# esp32_db_v0.net
KiCad netlist of a schematic drawn in EAGLE
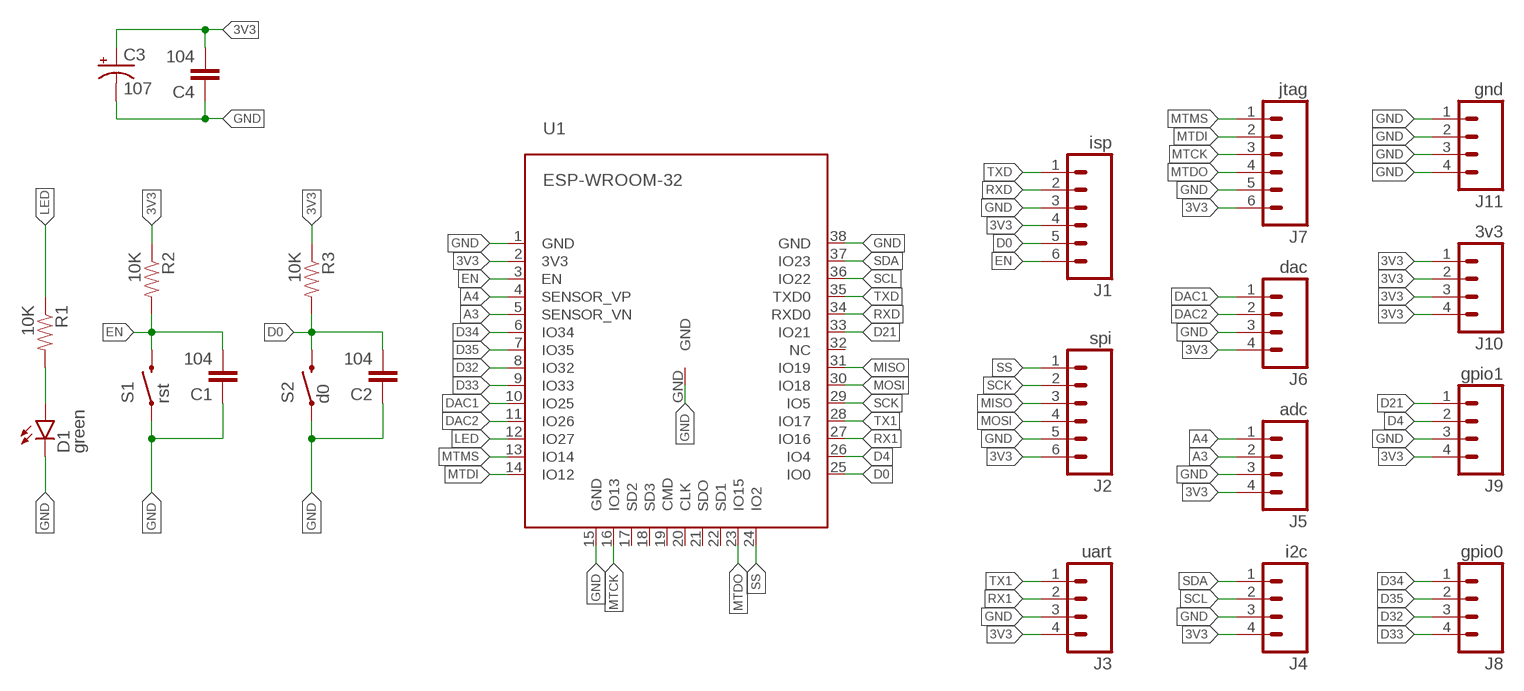
[diagram p0: schematic, sheet 1]

(export (version "E")
  (design (tool "Eeschema 10.0.6"))
  (components
    (comp (ref "C1")
      (value "104")
      (footprint "eagle-import:0603-CAP")
      (libsource (lib "eagle-import") (part "CAP0603-CAP"))
    )
    (comp (ref "C2")
      (value "104")
      (footprint "eagle-import:0603-CAP")
      (libsource (lib "eagle-import") (part "CAP0603-CAP"))
    )
    (comp (ref "C3")
      (value "107")
      (footprint "eagle-import:EIA3528-KIT")
      (libsource (lib "eagle-import") (part "CAP_POL3528-KIT"))
    )
    (comp (ref "C4")
      (value "104")
      (footprint "eagle-import:0603-CAP")
      (libsource (lib "eagle-import") (part "CAP0603-CAP"))
    )
    (comp (ref "D1")
      (value "green")
      (footprint "eagle-import:LED-0603-EASY")
      (libsource (lib "eagle-import") (part "LED-EASY"))
    )
    (comp (ref "J1")
      (value "isp")
      (footprint "eagle-import:1X06_NO_SILK")
      (libsource (lib "eagle-import") (part "M06NO_SILK_FEMALE_PTH"))
    )
    (comp (ref "J2")
      (value "spi")
      (footprint "eagle-import:1X06_NO_SILK")
      (libsource (lib "eagle-import") (part "M06NO_SILK_FEMALE_PTH"))
    )
    (comp (ref "J3")
      (value "uart")
      (footprint "eagle-import:1X04_NO_SILK_ALL_ROUND")
      (libsource (lib "eagle-import") (part "M04NO_SILK_ALL_ROUND"))
    )
    (comp (ref "J4")
      (value "i2c")
      (footprint "eagle-import:1X04_NO_SILK_ALL_ROUND")
      (libsource (lib "eagle-import") (part "M04NO_SILK_ALL_ROUND"))
    )
    (comp (ref "J5")
      (value "adc")
      (footprint "eagle-import:1X04_NO_SILK_ALL_ROUND")
      (libsource (lib "eagle-import") (part "M04NO_SILK_ALL_ROUND"))
    )
    (comp (ref "J6")
      (value "dac")
      (footprint "eagle-import:1X04_NO_SILK_ALL_ROUND")
      (libsource (lib "eagle-import") (part "M04NO_SILK_ALL_ROUND"))
    )
    (comp (ref "J7")
      (value "jtag")
      (footprint "eagle-import:1X06_NO_SILK")
      (libsource (lib "eagle-import") (part "M06NO_SILK_FEMALE_PTH"))
    )
    (comp (ref "J8")
      (value "gpio0")
      (footprint "eagle-import:1X04_NO_SILK_ALL_ROUND")
      (libsource (lib "eagle-import") (part "M04NO_SILK_ALL_ROUND"))
    )
    (comp (ref "J9")
      (value "gpio1")
      (footprint "eagle-import:1X04_NO_SILK_ALL_ROUND")
      (libsource (lib "eagle-import") (part "M04NO_SILK_ALL_ROUND"))
    )
    (comp (ref "J10")
      (value "3v3")
      (footprint "eagle-import:1X04_NO_SILK_ALL_ROUND")
      (libsource (lib "eagle-import") (part "M04NO_SILK_ALL_ROUND"))
    )
    (comp (ref "J11")
      (value "gnd")
      (footprint "eagle-import:1X04_NO_SILK_ALL_ROUND")
      (libsource (lib "eagle-import") (part "M04NO_SILK_ALL_ROUND"))
    )
    (comp (ref "R1")
      (value "10K")
      (footprint "eagle-import:0603-RES")
      (libsource (lib "eagle-import") (part "RESISTOR0603-RES"))
    )
    (comp (ref "R2")
      (value "10K")
      (footprint "eagle-import:0603-RES")
      (libsource (lib "eagle-import") (part "RESISTOR0603-RES"))
    )
    (comp (ref "R3")
      (value "10K")
      (footprint "eagle-import:0603-RES")
      (libsource (lib "eagle-import") (part "RESISTOR0603-RES"))
    )
    (comp (ref "S1")
      (value "rst")
      (footprint "eagle-import:TACTILE-PTH")
      (libsource (lib "eagle-import") (part "SWITCH-MOMENTARY-2PTH"))
    )
    (comp (ref "S2")
      (value "d0")
      (footprint "eagle-import:TACTILE-PTH")
      (libsource (lib "eagle-import") (part "SWITCH-MOMENTARY-2PTH"))
    )
    (comp (ref "U1")
      (value "ESP-WROOM-32")
      (footprint "eagle-import:ESP-WROOM-32")
      (libsource (lib "eagle-import") (part "ESP-WROOM-32"))
    )
  )
  (nets
    (net (code "1") (name "3V3") (class "Default")
      (node (ref "C3") (pin "A") (pinfunction "+_A") (pintype "passive"))
      (node (ref "C4") (pin "2") (pinfunction "2_2") (pintype "passive"))
      (node (ref "J1") (pin "4") (pinfunction "4_4") (pintype "passive"))
      (node (ref "J10") (pin "1") (pinfunction "1_1") (pintype "passive"))
      (node (ref "J10") (pin "2") (pinfunction "2_2") (pintype "passive"))
      (node (ref "J10") (pin "3") (pinfunction "3_3") (pintype "passive"))
      (node (ref "J10") (pin "4") (pinfunction "4_4") (pintype "passive"))
      (node (ref "J2") (pin "6") (pinfunction "6_6") (pintype "passive"))
      (node (ref "J3") (pin "4") (pinfunction "4_4") (pintype "passive"))
      (node (ref "J4") (pin "4") (pinfunction "4_4") (pintype "passive"))
      (node (ref "J5") (pin "4") (pinfunction "4_4") (pintype "passive"))
      (node (ref "J6") (pin "4") (pinfunction "4_4") (pintype "passive"))
      (node (ref "J7") (pin "6") (pinfunction "6_6") (pintype "passive"))
      (node (ref "J9") (pin "4") (pinfunction "4_4") (pintype "passive"))
      (node (ref "R2") (pin "1") (pinfunction "1_1") (pintype "passive"))
      (node (ref "R3") (pin "1") (pinfunction "1_1") (pintype "passive"))
      (node (ref "U1") (pin "2") (pinfunction "3V3_2") (pintype "bidirectional"))
    )
    (net (code "2") (name "A3") (class "Default")
      (node (ref "J5") (pin "2") (pinfunction "2_2") (pintype "passive"))
      (node (ref "U1") (pin "5") (pinfunction "SENSOR_VN_5") (pintype "bidirectional"))
    )
    (net (code "3") (name "A4") (class "Default")
      (node (ref "J5") (pin "1") (pinfunction "1_1") (pintype "passive"))
      (node (ref "U1") (pin "4") (pinfunction "SENSOR_VP_4") (pintype "bidirectional"))
    )
    (net (code "4") (name "D0") (class "Default")
      (node (ref "C2") (pin "2") (pinfunction "2_2") (pintype "passive"))
      (node (ref "J1") (pin "5") (pinfunction "5_5") (pintype "passive"))
      (node (ref "R3") (pin "2") (pinfunction "2_2") (pintype "passive"))
      (node (ref "S2") (pin "3") (pinfunction "2_3") (pintype "passive"))
      (node (ref "U1") (pin "25") (pinfunction "IO0_25") (pintype "bidirectional"))
    )
    (net (code "5") (name "D4") (class "Default")
      (node (ref "J9") (pin "2") (pinfunction "2_2") (pintype "passive"))
      (node (ref "U1") (pin "26") (pinfunction "IO4_26") (pintype "bidirectional"))
    )
    (net (code "6") (name "D21") (class "Default")
      (node (ref "J9") (pin "1") (pinfunction "1_1") (pintype "passive"))
      (node (ref "U1") (pin "33") (pinfunction "IO21_33") (pintype "bidirectional"))
    )
    (net (code "7") (name "D32") (class "Default")
      (node (ref "J8") (pin "3") (pinfunction "3_3") (pintype "passive"))
      (node (ref "U1") (pin "8") (pinfunction "IO32_8") (pintype "bidirectional"))
    )
    (net (code "8") (name "D33") (class "Default")
      (node (ref "J8") (pin "4") (pinfunction "4_4") (pintype "passive"))
      (node (ref "U1") (pin "9") (pinfunction "IO33_9") (pintype "bidirectional"))
    )
    (net (code "9") (name "D34") (class "Default")
      (node (ref "J8") (pin "1") (pinfunction "1_1") (pintype "passive"))
      (node (ref "U1") (pin "6") (pinfunction "IO34_6") (pintype "bidirectional"))
    )
    (net (code "10") (name "D35") (class "Default")
      (node (ref "J8") (pin "2") (pinfunction "2_2") (pintype "passive"))
      (node (ref "U1") (pin "7") (pinfunction "IO35_7") (pintype "bidirectional"))
    )
    (net (code "11") (name "DAC1") (class "Default")
      (node (ref "J6") (pin "1") (pinfunction "1_1") (pintype "passive"))
      (node (ref "U1") (pin "10") (pinfunction "IO25_10") (pintype "bidirectional"))
    )
    (net (code "12") (name "DAC2") (class "Default")
      (node (ref "J6") (pin "2") (pinfunction "2_2") (pintype "passive"))
      (node (ref "U1") (pin "11") (pinfunction "IO26_11") (pintype "bidirectional"))
    )
    (net (code "13") (name "EN") (class "Default")
      (node (ref "C1") (pin "2") (pinfunction "2_2") (pintype "passive"))
      (node (ref "J1") (pin "6") (pinfunction "6_6") (pintype "passive"))
      (node (ref "R2") (pin "2") (pinfunction "2_2") (pintype "passive"))
      (node (ref "S1") (pin "3") (pinfunction "2_3") (pintype "passive"))
      (node (ref "U1") (pin "3") (pinfunction "EN_3") (pintype "bidirectional"))
    )
    (net (code "14") (name "GND") (class "Default")
      (node (ref "C1") (pin "1") (pinfunction "1_1") (pintype "passive"))
      (node (ref "C2") (pin "1") (pinfunction "1_1") (pintype "passive"))
      (node (ref "C3") (pin "C") (pinfunction "-_C") (pintype "passive"))
      (node (ref "C4") (pin "1") (pinfunction "1_1") (pintype "passive"))
      (node (ref "D1") (pin "-") (pinfunction "C_-") (pintype "passive"))
      (node (ref "J1") (pin "3") (pinfunction "3_3") (pintype "passive"))
      (node (ref "J11") (pin "1") (pinfunction "1_1") (pintype "passive"))
      (node (ref "J11") (pin "2") (pinfunction "2_2") (pintype "passive"))
      (node (ref "J11") (pin "3") (pinfunction "3_3") (pintype "passive"))
      (node (ref "J11") (pin "4") (pinfunction "4_4") (pintype "passive"))
      (node (ref "J2") (pin "5") (pinfunction "5_5") (pintype "passive"))
      (node (ref "J3") (pin "3") (pinfunction "3_3") (pintype "passive"))
      (node (ref "J4") (pin "3") (pinfunction "3_3") (pintype "passive"))
      (node (ref "J5") (pin "3") (pinfunction "3_3") (pintype "passive"))
      (node (ref "J6") (pin "3") (pinfunction "3_3") (pintype "passive"))
      (node (ref "J7") (pin "5") (pinfunction "5_5") (pintype "passive"))
      (node (ref "J9") (pin "3") (pinfunction "3_3") (pintype "passive"))
      (node (ref "S1") (pin "1") (pinfunction "1_1") (pintype "passive"))
      (node (ref "S2") (pin "1") (pinfunction "1_1") (pintype "passive"))
      (node (ref "U1") (pin "1") (pinfunction "GND_1") (pintype "bidirectional"))
      (node (ref "U1") (pin "15") (pinfunction "GND_15") (pintype "bidirectional"))
      (node (ref "U1") (pin "38") (pinfunction "GND_38") (pintype "bidirectional"))
      (node (ref "U1") (pin "GND") (pinfunction "GND_GND") (pintype "bidirectional"))
    )
    (net (code "15") (name "LED") (class "Default")
      (node (ref "R1") (pin "1") (pinfunction "1_1") (pintype "passive"))
      (node (ref "U1") (pin "12") (pinfunction "IO27_12") (pintype "bidirectional"))
    )
    (net (code "16") (name "MISO") (class "Default")
      (node (ref "J2") (pin "3") (pinfunction "3_3") (pintype "passive"))
      (node (ref "U1") (pin "31") (pinfunction "IO19_31") (pintype "bidirectional"))
    )
    (net (code "17") (name "MOSI") (class "Default")
      (node (ref "J2") (pin "4") (pinfunction "4_4") (pintype "passive"))
      (node (ref "U1") (pin "30") (pinfunction "IO18_30") (pintype "bidirectional"))
    )
    (net (code "18") (name "MTCK") (class "Default")
      (node (ref "J7") (pin "3") (pinfunction "3_3") (pintype "passive"))
      (node (ref "U1") (pin "16") (pinfunction "IO13_16") (pintype "bidirectional"))
    )
    (net (code "19") (name "MTDI") (class "Default")
      (node (ref "J7") (pin "2") (pinfunction "2_2") (pintype "passive"))
      (node (ref "U1") (pin "14") (pinfunction "IO12_14") (pintype "bidirectional"))
    )
    (net (code "20") (name "MTDO") (class "Default")
      (node (ref "J7") (pin "4") (pinfunction "4_4") (pintype "passive"))
      (node (ref "U1") (pin "23") (pinfunction "IO15_23") (pintype "bidirectional"))
    )
    (net (code "21") (name "MTMS") (class "Default")
      (node (ref "J7") (pin "1") (pinfunction "1_1") (pintype "passive"))
      (node (ref "U1") (pin "13") (pinfunction "IO14_13") (pintype "bidirectional"))
    )
    (net (code "22") (name "Net-(D1-A)") (class "Default")
      (node (ref "D1") (pin "+") (pinfunction "A_+") (pintype "passive"))
      (node (ref "R1") (pin "2") (pinfunction "2_2") (pintype "passive"))
    )
    (net (code "23") (name "RX1") (class "Default")
      (node (ref "J3") (pin "2") (pinfunction "2_2") (pintype "passive"))
      (node (ref "U1") (pin "27") (pinfunction "IO16_27") (pintype "bidirectional"))
    )
    (net (code "24") (name "RXD") (class "Default")
      (node (ref "J1") (pin "2") (pinfunction "2_2") (pintype "passive"))
      (node (ref "U1") (pin "34") (pinfunction "RXD0_34") (pintype "bidirectional"))
    )
    (net (code "25") (name "SCK") (class "Default")
      (node (ref "J2") (pin "2") (pinfunction "2_2") (pintype "passive"))
      (node (ref "U1") (pin "29") (pinfunction "IO5_29") (pintype "bidirectional"))
    )
    (net (code "26") (name "SCL") (class "Default")
      (node (ref "J4") (pin "2") (pinfunction "2_2") (pintype "passive"))
      (node (ref "U1") (pin "36") (pinfunction "IO22_36") (pintype "bidirectional"))
    )
    (net (code "27") (name "SDA") (class "Default")
      (node (ref "J4") (pin "1") (pinfunction "1_1") (pintype "passive"))
      (node (ref "U1") (pin "37") (pinfunction "IO23_37") (pintype "bidirectional"))
    )
    (net (code "28") (name "SS") (class "Default")
      (node (ref "J2") (pin "1") (pinfunction "1_1") (pintype "passive"))
      (node (ref "U1") (pin "24") (pinfunction "IO2_24") (pintype "bidirectional"))
    )
    (net (code "29") (name "TX1") (class "Default")
      (node (ref "J3") (pin "1") (pinfunction "1_1") (pintype "passive"))
      (node (ref "U1") (pin "28") (pinfunction "IO17_28") (pintype "bidirectional"))
    )
    (net (code "30") (name "TXD") (class "Default")
      (node (ref "J1") (pin "1") (pinfunction "1_1") (pintype "passive"))
      (node (ref "U1") (pin "35") (pinfunction "TXD0_35") (pintype "bidirectional"))
    )
    (net (code "31") (name "unconnected-(U1-CLK-Pad20)") (class "Default")
      (node (ref "U1") (pin "20") (pinfunction "CLK_20") (pintype "bidirectional"))
    )
    (net (code "32") (name "unconnected-(U1-CMD-Pad19)") (class "Default")
      (node (ref "U1") (pin "19") (pinfunction "CMD_19") (pintype "bidirectional"))
    )
    (net (code "33") (name "unconnected-(U1-NC-Pad32)") (class "Default")
      (node (ref "U1") (pin "32") (pinfunction "NC_32") (pintype "bidirectional"))
    )
    (net (code "34") (name "unconnected-(U1-SD1-Pad22)") (class "Default")
      (node (ref "U1") (pin "22") (pinfunction "SD1_22") (pintype "bidirectional"))
    )
    (net (code "35") (name "unconnected-(U1-SD2-Pad17)") (class "Default")
      (node (ref "U1") (pin "17") (pinfunction "SD2_17") (pintype "bidirectional"))
    )
    (net (code "36") (name "unconnected-(U1-SD3-Pad18)") (class "Default")
      (node (ref "U1") (pin "18") (pinfunction "SD3_18") (pintype "bidirectional"))
    )
    (net (code "37") (name "unconnected-(U1-SDO-Pad21)") (class "Default")
      (node (ref "U1") (pin "21") (pinfunction "SDO_21") (pintype "bidirectional"))
    )
  )
)
